# ss.net
KiCad netlist of a schematic drawn in Altium Designer
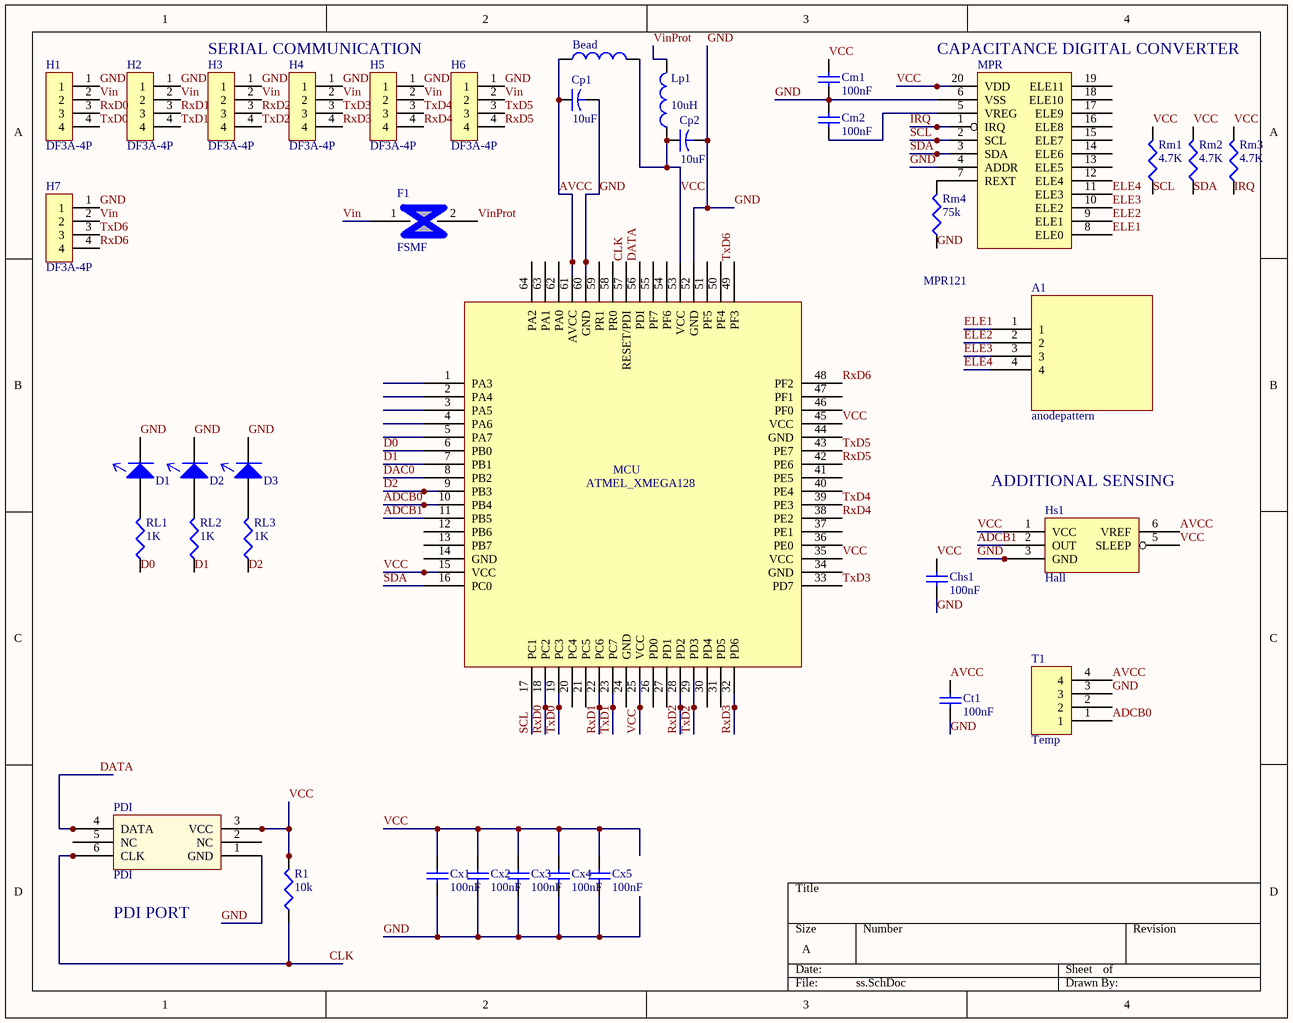
[diagram p0: ss.SchDoc]

(export (version "E")
  (design (tool "Eeschema 10.0.6"))
  (components
    (comp (ref "A1")
      (value "anodepattern")
      (footprint "anodepattern")
      (libsource (lib "anodepattern") (part "anodepattern"))
    )
    (comp (ref "Bead")
      (value "~")
      (footprint "C0402-DRL")
      (description "Inductor")
      (fields (field (name "PUBLISHER") "Altium Limited"))
      (libsource (lib "Miscellaneous Devices") (part "Inductor"))
    )
    (comp (ref "Chs1")
      (value "100nF")
      (footprint "C0402-DRL")
      (description "Capacitor")
      (fields (field (name "PUBLISHER") "Altium Limited"))
      (libsource (lib "Miscellaneous Devices") (part "Cap"))
    )
    (comp (ref "Cm1")
      (value "100nF")
      (footprint "C0402-DRL")
      (description "Capacitor")
      (fields (field (name "PUBLISHER") "Altium Limited"))
      (libsource (lib "Miscellaneous Devices") (part "Cap"))
    )
    (comp (ref "Cm2")
      (value "100nF")
      (footprint "C0402-DRL")
      (description "Capacitor")
      (fields (field (name "PUBLISHER") "Altium Limited"))
      (libsource (lib "Miscellaneous Devices") (part "Cap"))
    )
    (comp (ref "Cp1")
      (value "10uF")
      (footprint "C0603-DRL")
      (description "Capacitor")
      (fields (field (name "PUBLISHER") "Altium Limited"))
      (libsource (lib "Miscellaneous Devices") (part "Cap2"))
    )
    (comp (ref "Cp2")
      (value "10uF")
      (footprint "C0603-DRL")
      (description "Capacitor")
      (fields (field (name "PUBLISHER") "Altium Limited"))
      (libsource (lib "Miscellaneous Devices") (part "Cap2"))
    )
    (comp (ref "Ct1")
      (value "100nF")
      (footprint "C0402-DRL")
      (description "Capacitor")
      (fields (field (name "PUBLISHER") "Altium Limited"))
      (libsource (lib "Miscellaneous Devices") (part "Cap"))
    )
    (comp (ref "Cx1")
      (value "100nF")
      (footprint "C0402-DRL")
      (description "Capacitor")
      (fields (field (name "PUBLISHER") "Altium Limited"))
      (libsource (lib "Miscellaneous Devices") (part "Cap"))
    )
    (comp (ref "Cx2")
      (value "100nF")
      (footprint "C0402-DRL")
      (description "Capacitor")
      (fields (field (name "PUBLISHER") "Altium Limited"))
      (libsource (lib "Miscellaneous Devices") (part "Cap"))
    )
    (comp (ref "Cx3")
      (value "100nF")
      (footprint "C0402-DRL")
      (description "Capacitor")
      (fields (field (name "PUBLISHER") "Altium Limited"))
      (libsource (lib "Miscellaneous Devices") (part "Cap"))
    )
    (comp (ref "Cx4")
      (value "100nF")
      (footprint "C0402-DRL")
      (description "Capacitor")
      (fields (field (name "PUBLISHER") "Altium Limited"))
      (libsource (lib "Miscellaneous Devices") (part "Cap"))
    )
    (comp (ref "Cx5")
      (value "100nF")
      (footprint "C0402-DRL")
      (description "Capacitor")
      (fields (field (name "PUBLISHER") "Altium Limited"))
      (libsource (lib "Miscellaneous Devices") (part "Cap"))
    )
    (comp (ref "D1")
      (value "LEDSMD")
      (footprint "D1206-DRL")
      (description "LED")
      (libsource (lib "test1") (part "LEDSMD"))
    )
    (comp (ref "D2")
      (value "LEDSMD")
      (footprint "D1206-DRL")
      (description "LED")
      (libsource (lib "test1") (part "LEDSMD"))
    )
    (comp (ref "D3")
      (value "LEDSMD")
      (footprint "D1206-DRL")
      (description "LED")
      (libsource (lib "test1") (part "LEDSMD"))
    )
    (comp (ref "F1")
      (value "FSMF")
      (footprint "C0603-DRL")
      (description "Fuse PTC Reset")
      (libsource (lib "test1") (part "FSMF"))
    )
    (comp (ref "H1")
      (value "DF3A-4P")
      (footprint "UART")
      (description "4pin header")
      (libsource (lib "hirose") (part "DF3A-4P"))
    )
    (comp (ref "H2")
      (value "DF3A-4P")
      (footprint "UART")
      (description "4pin header")
      (libsource (lib "hirose") (part "DF3A-4P"))
    )
    (comp (ref "H3")
      (value "DF3A-4P")
      (footprint "UART")
      (description "4pin header")
      (libsource (lib "hirose") (part "DF3A-4P"))
    )
    (comp (ref "H4")
      (value "DF3A-4P")
      (footprint "UART")
      (description "4pin header")
      (libsource (lib "hirose") (part "DF3A-4P"))
    )
    (comp (ref "H5")
      (value "DF3A-4P")
      (footprint "UART")
      (description "4pin header")
      (libsource (lib "hirose") (part "DF3A-4P"))
    )
    (comp (ref "H6")
      (value "DF3A-4P")
      (footprint "UART")
      (description "4pin header")
      (libsource (lib "hirose") (part "DF3A-4P"))
    )
    (comp (ref "H7")
      (value "DF3A-4P")
      (footprint "UART")
      (description "4pin header")
      (libsource (lib "hirose") (part "DF3A-4P"))
    )
    (comp (ref "Hs1")
      (value "Hall")
      (footprint "HALL")
      (description "620-11-ND Hall Effect")
      (libsource (lib "ss") (part "Hall"))
    )
    (comp (ref "Lp1")
      (value "10uH")
      (footprint "C0603-DRL")
      (description "Inductor")
      (fields (field (name "PUBLISHER") "Altium Limited"))
      (libsource (lib "Miscellaneous Devices") (part "Inductor"))
    )
    (comp (ref "MCU")
      (value "ATMEL_XMEGA128")
      (footprint "QFN50P900X900X100-64N")
      (libsource (lib "atmel") (part "ATMEL_XMEGA128"))
    )
    (comp (ref "MPR")
      (value "MPR121")
      (footprint "QFN40P300X300X60-20N")
      (libsource (lib "ss") (part "MPR121"))
    )
    (comp (ref "PDI") (value "PDI") (footprint "PDI_SMT") (libsource (lib "atmel") (part "PDI")))
    (comp (ref "R1")
      (value "10k")
      (footprint "R0402-DRL")
      (description "Resistor")
      (fields (field (name "Comment") "R") (field (name "PUBLISHER") "Altium Limited"))
      (libsource (lib "standard") (part "R"))
    )
    (comp (ref "RL1")
      (value "1K")
      (footprint "R0402-DRL")
      (description "Resistor")
      (fields (field (name "Comment") "R") (field (name "PUBLISHER") "Altium Limited"))
      (libsource (lib "standard") (part "R"))
    )
    (comp (ref "RL2")
      (value "1K")
      (footprint "R0402-DRL")
      (description "Resistor")
      (fields (field (name "Comment") "R") (field (name "PUBLISHER") "Altium Limited"))
      (libsource (lib "standard") (part "R"))
    )
    (comp (ref "RL3")
      (value "1K")
      (footprint "R0402-DRL")
      (description "Resistor")
      (fields (field (name "Comment") "R") (field (name "PUBLISHER") "Altium Limited"))
      (libsource (lib "standard") (part "R"))
    )
    (comp (ref "Rm1")
      (value "4.7K")
      (footprint "R0402-DRL")
      (description "Resistor")
      (fields (field (name "Comment") "R") (field (name "PUBLISHER") "Altium Limited"))
      (libsource (lib "standard") (part "R"))
    )
    (comp (ref "Rm2")
      (value "4.7K")
      (footprint "R0402-DRL")
      (description "Resistor")
      (fields (field (name "Comment") "R") (field (name "PUBLISHER") "Altium Limited"))
      (libsource (lib "standard") (part "R"))
    )
    (comp (ref "Rm3")
      (value "4.7K")
      (footprint "R0402-DRL")
      (description "Resistor")
      (fields (field (name "Comment") "R") (field (name "PUBLISHER") "Altium Limited"))
      (libsource (lib "standard") (part "R"))
    )
    (comp (ref "Rm4")
      (value "75k")
      (footprint "R0603-DRL")
      (description "Resistor")
      (fields (field (name "Comment") "R") (field (name "PUBLISHER") "Altium Limited"))
      (libsource (lib "standard") (part "R"))
    )
    (comp (ref "T1")
      (value "Temp")
      (footprint "QFN50P100X130X55-4N")
      (description "497-5814-1-ND Temperature sensor")
      (libsource (lib "ss") (part "Temp"))
    )
  )
  (nets
    (net (code "1") (name "/ADCB0") (class "Default")
      (node (ref "MCU") (pin "10") (pinfunction "PB4_10") (pintype "passive"))
      (node (ref "T1") (pin "1") (pinfunction "1_1") (pintype "passive"))
    )
    (net (code "2") (name "/ADCB1") (class "Default")
      (node (ref "Hs1") (pin "2") (pinfunction "OUT_2") (pintype "passive"))
      (node (ref "MCU") (pin "11") (pinfunction "PB5_11") (pintype "passive"))
    )
    (net (code "3") (name "/AVCC") (class "Default")
      (node (ref "Bead") (pin "1") (pinfunction "1_1") (pintype "passive"))
      (node (ref "Cp1") (pin "1") (pinfunction "1_1") (pintype "passive"))
      (node (ref "Ct1") (pin "2") (pinfunction "2_2") (pintype "passive"))
      (node (ref "Hs1") (pin "6") (pinfunction "VREF_6") (pintype "passive"))
      (node (ref "MCU") (pin "61") (pinfunction "AVCC_61") (pintype "passive"))
      (node (ref "T1") (pin "4") (pinfunction "4_4") (pintype "passive"))
    )
    (net (code "4") (name "/CLK") (class "Default")
      (node (ref "MCU") (pin "57") (pinfunction "RESET/PDI_57") (pintype "passive"))
      (node (ref "PDI") (pin "6") (pinfunction "CLK_6") (pintype "passive"))
      (node (ref "R1") (pin "1") (pinfunction "1_1") (pintype "passive"))
    )
    (net (code "5") (name "/D0") (class "Default")
      (node (ref "MCU") (pin "6") (pinfunction "PB0_6") (pintype "passive"))
      (node (ref "RL1") (pin "1") (pinfunction "1_1") (pintype "passive"))
    )
    (net (code "6") (name "/D1") (class "Default")
      (node (ref "MCU") (pin "7") (pinfunction "PB1_7") (pintype "passive"))
      (node (ref "RL2") (pin "1") (pinfunction "1_1") (pintype "passive"))
    )
    (net (code "7") (name "/D2") (class "Default")
      (node (ref "MCU") (pin "9") (pinfunction "PB3_9") (pintype "passive"))
      (node (ref "RL3") (pin "1") (pinfunction "1_1") (pintype "passive"))
    )
    (net (code "8") (name "/DAC0") (class "Default")
      (node (ref "MCU") (pin "8") (pinfunction "PB2_8") (pintype "passive"))
    )
    (net (code "9") (name "/DATA") (class "Default")
      (node (ref "MCU") (pin "56") (pinfunction "PDI_56") (pintype "passive"))
      (node (ref "PDI") (pin "4") (pinfunction "DATA_4") (pintype "passive"))
    )
    (net (code "10") (name "/ELE1") (class "Default")
      (node (ref "A1") (pin "1") (pinfunction "1_1") (pintype "passive"))
      (node (ref "MPR") (pin "8") (pinfunction "ELE0_8") (pintype "passive"))
    )
    (net (code "11") (name "/ELE2") (class "Default")
      (node (ref "A1") (pin "2") (pinfunction "2_2") (pintype "passive"))
      (node (ref "MPR") (pin "9") (pinfunction "ELE1_9") (pintype "passive"))
    )
    (net (code "12") (name "/ELE3") (class "Default")
      (node (ref "A1") (pin "3") (pinfunction "3_3") (pintype "passive"))
      (node (ref "MPR") (pin "10") (pinfunction "ELE2_10") (pintype "passive"))
    )
    (net (code "13") (name "/ELE4") (class "Default")
      (node (ref "A1") (pin "4") (pinfunction "4_4") (pintype "passive"))
      (node (ref "MPR") (pin "11") (pinfunction "ELE3_11") (pintype "passive"))
    )
    (net (code "14") (name "/GND") (class "Default")
      (node (ref "Chs1") (pin "1") (pinfunction "1_1") (pintype "passive"))
      (node (ref "Cm1") (pin "1") (pinfunction "1_1") (pintype "passive"))
      (node (ref "Cm2") (pin "1") (pinfunction "1_1") (pintype "passive"))
      (node (ref "Cp1") (pin "2") (pinfunction "2_2") (pintype "passive"))
      (node (ref "Cp2") (pin "2") (pinfunction "2_2") (pintype "passive"))
      (node (ref "Ct1") (pin "1") (pinfunction "1_1") (pintype "passive"))
      (node (ref "Cx1") (pin "1") (pinfunction "1_1") (pintype "passive"))
      (node (ref "Cx2") (pin "1") (pinfunction "1_1") (pintype "passive"))
      (node (ref "Cx3") (pin "1") (pinfunction "1_1") (pintype "passive"))
      (node (ref "Cx4") (pin "1") (pinfunction "1_1") (pintype "passive"))
      (node (ref "Cx5") (pin "1") (pinfunction "1_1") (pintype "passive"))
      (node (ref "D1") (pin "1") (pinfunction "K_1") (pintype "passive"))
      (node (ref "D2") (pin "1") (pinfunction "K_1") (pintype "passive"))
      (node (ref "D3") (pin "1") (pinfunction "K_1") (pintype "passive"))
      (node (ref "H1") (pin "1") (pinfunction "1_1") (pintype "passive"))
      (node (ref "H2") (pin "1") (pinfunction "1_1") (pintype "passive"))
      (node (ref "H3") (pin "1") (pinfunction "1_1") (pintype "passive"))
      (node (ref "H4") (pin "1") (pinfunction "1_1") (pintype "passive"))
      (node (ref "H5") (pin "1") (pinfunction "1_1") (pintype "passive"))
      (node (ref "H6") (pin "1") (pinfunction "1_1") (pintype "passive"))
      (node (ref "H7") (pin "1") (pinfunction "1_1") (pintype "passive"))
      (node (ref "Hs1") (pin "3") (pinfunction "GND_3") (pintype "passive"))
      (node (ref "MCU") (pin "52") (pinfunction "GND_52") (pintype "passive"))
      (node (ref "MCU") (pin "60") (pinfunction "GND_60") (pintype "passive"))
      (node (ref "MPR") (pin "4") (pinfunction "ADDR_4") (pintype "passive"))
      (node (ref "MPR") (pin "6") (pinfunction "VSS_6") (pintype "passive"))
      (node (ref "PDI") (pin "1") (pinfunction "GND_1") (pintype "passive"))
      (node (ref "Rm4") (pin "1") (pinfunction "1_1") (pintype "passive"))
      (node (ref "T1") (pin "3") (pinfunction "3_3") (pintype "passive"))
    )
    (net (code "15") (name "/IRQ") (class "Default")
      (node (ref "MPR") (pin "1") (pinfunction "IRQ_1") (pintype "passive"))
      (node (ref "Rm3") (pin "1") (pinfunction "1_1") (pintype "passive"))
    )
    (net (code "16") (name "/RxD0") (class "Default")
      (node (ref "H1") (pin "3") (pinfunction "3_3") (pintype "passive"))
      (node (ref "MCU") (pin "18") (pinfunction "PC2_18") (pintype "passive"))
    )
    (net (code "17") (name "/RxD1") (class "Default")
      (node (ref "H2") (pin "3") (pinfunction "3_3") (pintype "passive"))
      (node (ref "MCU") (pin "22") (pinfunction "PC6_22") (pintype "passive"))
    )
    (net (code "18") (name "/RxD2") (class "Default")
      (node (ref "H3") (pin "3") (pinfunction "3_3") (pintype "passive"))
      (node (ref "MCU") (pin "28") (pinfunction "PD2_28") (pintype "passive"))
    )
    (net (code "19") (name "/RxD3") (class "Default")
      (node (ref "H4") (pin "4") (pinfunction "4_4") (pintype "passive"))
      (node (ref "MCU") (pin "32") (pinfunction "PD6_32") (pintype "passive"))
    )
    (net (code "20") (name "/RxD4") (class "Default")
      (node (ref "H5") (pin "4") (pinfunction "4_4") (pintype "passive"))
      (node (ref "MCU") (pin "38") (pinfunction "PE2_38") (pintype "passive"))
    )
    (net (code "21") (name "/RxD5") (class "Default")
      (node (ref "H6") (pin "4") (pinfunction "4_4") (pintype "passive"))
      (node (ref "MCU") (pin "42") (pinfunction "PE6_42") (pintype "passive"))
    )
    (net (code "22") (name "/RxD6") (class "Default")
      (node (ref "H7") (pin "4") (pinfunction "4_4") (pintype "passive"))
      (node (ref "MCU") (pin "48") (pinfunction "PF2_48") (pintype "passive"))
    )
    (net (code "23") (name "/SCL") (class "Default")
      (node (ref "MCU") (pin "17") (pinfunction "PC1_17") (pintype "passive"))
      (node (ref "MPR") (pin "2") (pinfunction "SCL_2") (pintype "passive"))
      (node (ref "Rm1") (pin "1") (pinfunction "1_1") (pintype "passive"))
    )
    (net (code "24") (name "/SDA") (class "Default")
      (node (ref "MCU") (pin "16") (pinfunction "PC0_16") (pintype "passive"))
      (node (ref "MPR") (pin "3") (pinfunction "SDA_3") (pintype "passive"))
      (node (ref "Rm2") (pin "1") (pinfunction "1_1") (pintype "passive"))
    )
    (net (code "25") (name "/TxD0") (class "Default")
      (node (ref "H1") (pin "4") (pinfunction "4_4") (pintype "passive"))
      (node (ref "MCU") (pin "19") (pinfunction "PC3_19") (pintype "passive"))
    )
    (net (code "26") (name "/TxD1") (class "Default")
      (node (ref "H2") (pin "4") (pinfunction "4_4") (pintype "passive"))
      (node (ref "MCU") (pin "23") (pinfunction "PC7_23") (pintype "passive"))
    )
    (net (code "27") (name "/TxD2") (class "Default")
      (node (ref "H3") (pin "4") (pinfunction "4_4") (pintype "passive"))
      (node (ref "MCU") (pin "29") (pinfunction "PD3_29") (pintype "passive"))
    )
    (net (code "28") (name "/TxD3") (class "Default")
      (node (ref "H4") (pin "3") (pinfunction "3_3") (pintype "passive"))
      (node (ref "MCU") (pin "33") (pinfunction "PD7_33") (pintype "passive"))
    )
    (net (code "29") (name "/TxD4") (class "Default")
      (node (ref "H5") (pin "3") (pinfunction "3_3") (pintype "passive"))
      (node (ref "MCU") (pin "39") (pinfunction "PE3_39") (pintype "passive"))
    )
    (net (code "30") (name "/TxD5") (class "Default")
      (node (ref "H6") (pin "3") (pinfunction "3_3") (pintype "passive"))
      (node (ref "MCU") (pin "43") (pinfunction "PE7_43") (pintype "passive"))
    )
    (net (code "31") (name "/TxD6") (class "Default")
      (node (ref "H7") (pin "3") (pinfunction "3_3") (pintype "passive"))
      (node (ref "MCU") (pin "49") (pinfunction "PF3_49") (pintype "passive"))
    )
    (net (code "32") (name "/VCC") (class "Default")
      (node (ref "Bead") (pin "2") (pinfunction "2_2") (pintype "passive"))
      (node (ref "Chs1") (pin "2") (pinfunction "2_2") (pintype "passive"))
      (node (ref "Cm1") (pin "2") (pinfunction "2_2") (pintype "passive"))
      (node (ref "Cp2") (pin "1") (pinfunction "1_1") (pintype "passive"))
      (node (ref "Cx1") (pin "2") (pinfunction "2_2") (pintype "passive"))
      (node (ref "Cx2") (pin "2") (pinfunction "2_2") (pintype "passive"))
      (node (ref "Cx3") (pin "2") (pinfunction "2_2") (pintype "passive"))
      (node (ref "Cx4") (pin "2") (pinfunction "2_2") (pintype "passive"))
      (node (ref "Cx5") (pin "2") (pinfunction "2_2") (pintype "passive"))
      (node (ref "Hs1") (pin "1") (pinfunction "VCC_1") (pintype "passive"))
      (node (ref "Hs1") (pin "5") (pinfunction "SLEEP_5") (pintype "passive"))
      (node (ref "Lp1") (pin "1") (pinfunction "1_1") (pintype "passive"))
      (node (ref "MCU") (pin "15") (pinfunction "VCC_15") (pintype "passive"))
      (node (ref "MCU") (pin "25") (pinfunction "VCC_25") (pintype "passive"))
      (node (ref "MCU") (pin "35") (pinfunction "VCC_35") (pintype "passive"))
      (node (ref "MCU") (pin "45") (pinfunction "VCC_45") (pintype "passive"))
      (node (ref "MCU") (pin "53") (pinfunction "VCC_53") (pintype "passive"))
      (node (ref "MPR") (pin "20") (pinfunction "VDD_20") (pintype "passive"))
      (node (ref "PDI") (pin "3") (pinfunction "VCC_3") (pintype "passive"))
      (node (ref "R1") (pin "2") (pinfunction "2_2") (pintype "passive"))
      (node (ref "Rm1") (pin "2") (pinfunction "2_2") (pintype "passive"))
      (node (ref "Rm2") (pin "2") (pinfunction "2_2") (pintype "passive"))
      (node (ref "Rm3") (pin "2") (pinfunction "2_2") (pintype "passive"))
    )
    (net (code "33") (name "/Vin") (class "Default")
      (node (ref "F1") (pin "1") (pinfunction "1_1") (pintype "passive"))
      (node (ref "H1") (pin "2") (pinfunction "2_2") (pintype "passive"))
      (node (ref "H2") (pin "2") (pinfunction "2_2") (pintype "passive"))
      (node (ref "H3") (pin "2") (pinfunction "2_2") (pintype "passive"))
      (node (ref "H4") (pin "2") (pinfunction "2_2") (pintype "passive"))
      (node (ref "H5") (pin "2") (pinfunction "2_2") (pintype "passive"))
      (node (ref "H6") (pin "2") (pinfunction "2_2") (pintype "passive"))
      (node (ref "H7") (pin "2") (pinfunction "2_2") (pintype "passive"))
    )
    (net (code "34") (name "/VinProt") (class "Default")
      (node (ref "F1") (pin "2") (pinfunction "2_2") (pintype "passive"))
      (node (ref "Lp1") (pin "2") (pinfunction "2_2") (pintype "passive"))
    )
    (net (code "35") (name "Net-(D1-A)") (class "Default")
      (node (ref "D1") (pin "2") (pinfunction "A_2") (pintype "passive"))
      (node (ref "RL1") (pin "2") (pinfunction "2_2") (pintype "passive"))
    )
    (net (code "36") (name "Net-(D2-A)") (class "Default")
      (node (ref "D2") (pin "2") (pinfunction "A_2") (pintype "passive"))
      (node (ref "RL2") (pin "2") (pinfunction "2_2") (pintype "passive"))
    )
    (net (code "37") (name "Net-(D3-A)") (class "Default")
      (node (ref "D3") (pin "2") (pinfunction "A_2") (pintype "passive"))
      (node (ref "RL3") (pin "2") (pinfunction "2_2") (pintype "passive"))
    )
    (net (code "38") (name "Net-(MPR-REXT)") (class "Default")
      (node (ref "MPR") (pin "7") (pinfunction "REXT_7") (pintype "passive"))
      (node (ref "Rm4") (pin "2") (pinfunction "2_2") (pintype "passive"))
    )
    (net (code "39") (name "Net-(MPR-VREG)") (class "Default")
      (node (ref "Cm2") (pin "2") (pinfunction "2_2") (pintype "passive"))
      (node (ref "MPR") (pin "5") (pinfunction "VREG_5") (pintype "passive"))
    )
    (net (code "40") (name "unconnected-(MCU-GND-Pad14)") (class "Default")
      (node (ref "MCU") (pin "14") (pinfunction "GND_14") (pintype "passive"))
    )
    (net (code "41") (name "unconnected-(MCU-GND-Pad24)") (class "Default")
      (node (ref "MCU") (pin "24") (pinfunction "GND_24") (pintype "passive"))
    )
    (net (code "42") (name "unconnected-(MCU-GND-Pad34)") (class "Default")
      (node (ref "MCU") (pin "34") (pinfunction "GND_34") (pintype "passive"))
    )
    (net (code "43") (name "unconnected-(MCU-GND-Pad44)") (class "Default")
      (node (ref "MCU") (pin "44") (pinfunction "GND_44") (pintype "passive"))
    )
    (net (code "44") (name "unconnected-(MCU-PA0-Pad62)") (class "Default")
      (node (ref "MCU") (pin "62") (pinfunction "PA0_62") (pintype "passive"))
    )
    (net (code "45") (name "unconnected-(MCU-PA1-Pad63)") (class "Default")
      (node (ref "MCU") (pin "63") (pinfunction "PA1_63") (pintype "passive"))
    )
    (net (code "46") (name "unconnected-(MCU-PA2-Pad64)") (class "Default")
      (node (ref "MCU") (pin "64") (pinfunction "PA2_64") (pintype "passive"))
    )
    (net (code "47") (name "unconnected-(MCU-PA3-Pad1)") (class "Default")
      (node (ref "MCU") (pin "1") (pinfunction "PA3_1") (pintype "passive"))
    )
    (net (code "48") (name "unconnected-(MCU-PA4-Pad2)") (class "Default")
      (node (ref "MCU") (pin "2") (pinfunction "PA4_2") (pintype "passive"))
    )
    (net (code "49") (name "unconnected-(MCU-PA5-Pad3)") (class "Default")
      (node (ref "MCU") (pin "3") (pinfunction "PA5_3") (pintype "passive"))
    )
    (net (code "50") (name "unconnected-(MCU-PA6-Pad4)") (class "Default")
      (node (ref "MCU") (pin "4") (pinfunction "PA6_4") (pintype "passive"))
    )
    (net (code "51") (name "unconnected-(MCU-PA7-Pad5)") (class "Default")
      (node (ref "MCU") (pin "5") (pinfunction "PA7_5") (pintype "passive"))
    )
    (net (code "52") (name "unconnected-(MCU-PB6-Pad12)") (class "Default")
      (node (ref "MCU") (pin "12") (pinfunction "PB6_12") (pintype "passive"))
    )
    (net (code "53") (name "unconnected-(MCU-PB7-Pad13)") (class "Default")
      (node (ref "MCU") (pin "13") (pinfunction "PB7_13") (pintype "passive"))
    )
    (net (code "54") (name "unconnected-(MCU-PC4-Pad20)") (class "Default")
      (node (ref "MCU") (pin "20") (pinfunction "PC4_20") (pintype "passive"))
    )
    (net (code "55") (name "unconnected-(MCU-PC5-Pad21)") (class "Default")
      (node (ref "MCU") (pin "21") (pinfunction "PC5_21") (pintype "passive"))
    )
    (net (code "56") (name "unconnected-(MCU-PD0-Pad26)") (class "Default")
      (node (ref "MCU") (pin "26") (pinfunction "PD0_26") (pintype "passive"))
    )
    (net (code "57") (name "unconnected-(MCU-PD1-Pad27)") (class "Default")
      (node (ref "MCU") (pin "27") (pinfunction "PD1_27") (pintype "passive"))
    )
    (net (code "58") (name "unconnected-(MCU-PD4-Pad30)") (class "Default")
      (node (ref "MCU") (pin "30") (pinfunction "PD4_30") (pintype "passive"))
    )
    (net (code "59") (name "unconnected-(MCU-PD5-Pad31)") (class "Default")
      (node (ref "MCU") (pin "31") (pinfunction "PD5_31") (pintype "passive"))
    )
    (net (code "60") (name "unconnected-(MCU-PE0-Pad36)") (class "Default")
      (node (ref "MCU") (pin "36") (pinfunction "PE0_36") (pintype "passive"))
    )
    (net (code "61") (name "unconnected-(MCU-PE1-Pad37)") (class "Default")
      (node (ref "MCU") (pin "37") (pinfunction "PE1_37") (pintype "passive"))
    )
    (net (code "62") (name "unconnected-(MCU-PE4-Pad40)") (class "Default")
      (node (ref "MCU") (pin "40") (pinfunction "PE4_40") (pintype "passive"))
    )
    (net (code "63") (name "unconnected-(MCU-PE5-Pad41)") (class "Default")
      (node (ref "MCU") (pin "41") (pinfunction "PE5_41") (pintype "passive"))
    )
    (net (code "64") (name "unconnected-(MCU-PF0-Pad46)") (class "Default")
      (node (ref "MCU") (pin "46") (pinfunction "PF0_46") (pintype "passive"))
    )
    (net (code "65") (name "unconnected-(MCU-PF1-Pad47)") (class "Default")
      (node (ref "MCU") (pin "47") (pinfunction "PF1_47") (pintype "passive"))
    )
    (net (code "66") (name "unconnected-(MCU-PF4-Pad50)") (class "Default")
      (node (ref "MCU") (pin "50") (pinfunction "PF4_50") (pintype "passive"))
    )
    (net (code "67") (name "unconnected-(MCU-PF5-Pad51)") (class "Default")
      (node (ref "MCU") (pin "51") (pinfunction "PF5_51") (pintype "passive"))
    )
    (net (code "68") (name "unconnected-(MCU-PF6-Pad54)") (class "Default")
      (node (ref "MCU") (pin "54") (pinfunction "PF6_54") (pintype "passive"))
    )
    (net (code "69") (name "unconnected-(MCU-PF7-Pad55)") (class "Default")
      (node (ref "MCU") (pin "55") (pinfunction "PF7_55") (pintype "passive"))
    )
    (net (code "70") (name "unconnected-(MCU-PR0-Pad58)") (class "Default")
      (node (ref "MCU") (pin "58") (pinfunction "PR0_58") (pintype "passive"))
    )
    (net (code "71") (name "unconnected-(MCU-PR1-Pad59)") (class "Default")
      (node (ref "MCU") (pin "59") (pinfunction "PR1_59") (pintype "passive"))
    )
    (net (code "72") (name "unconnected-(MPR-ELE4-Pad12)") (class "Default")
      (node (ref "MPR") (pin "12") (pinfunction "ELE4_12") (pintype "passive"))
    )
    (net (code "73") (name "unconnected-(MPR-ELE5-Pad13)") (class "Default")
      (node (ref "MPR") (pin "13") (pinfunction "ELE5_13") (pintype "passive"))
    )
    (net (code "74") (name "unconnected-(MPR-ELE6-Pad14)") (class "Default")
      (node (ref "MPR") (pin "14") (pinfunction "ELE6_14") (pintype "passive"))
    )
    (net (code "75") (name "unconnected-(MPR-ELE7-Pad15)") (class "Default")
      (node (ref "MPR") (pin "15") (pinfunction "ELE7_15") (pintype "passive"))
    )
    (net (code "76") (name "unconnected-(MPR-ELE8-Pad16)") (class "Default")
      (node (ref "MPR") (pin "16") (pinfunction "ELE8_16") (pintype "passive"))
    )
    (net (code "77") (name "unconnected-(MPR-ELE9-Pad17)") (class "Default")
      (node (ref "MPR") (pin "17") (pinfunction "ELE9_17") (pintype "passive"))
    )
    (net (code "78") (name "unconnected-(MPR-ELE10-Pad18)") (class "Default")
      (node (ref "MPR") (pin "18") (pinfunction "ELE10_18") (pintype "passive"))
    )
    (net (code "79") (name "unconnected-(MPR-ELE11-Pad19)") (class "Default")
      (node (ref "MPR") (pin "19") (pinfunction "ELE11_19") (pintype "passive"))
    )
    (net (code "80") (name "unconnected-(PDI-NC-Pad2)") (class "Default")
      (node (ref "PDI") (pin "2") (pinfunction "NC_2") (pintype "passive"))
    )
    (net (code "81") (name "unconnected-(PDI-NC-Pad5)") (class "Default")
      (node (ref "PDI") (pin "5") (pinfunction "NC_5") (pintype "passive"))
    )
    (net (code "82") (name "unconnected-(T1-Pad2)") (class "Default")
      (node (ref "T1") (pin "2") (pinfunction "2_2") (pintype "passive"))
    )
  )
)
